# esp32.net
KiCad netlist of a schematic drawn in Altium Designer
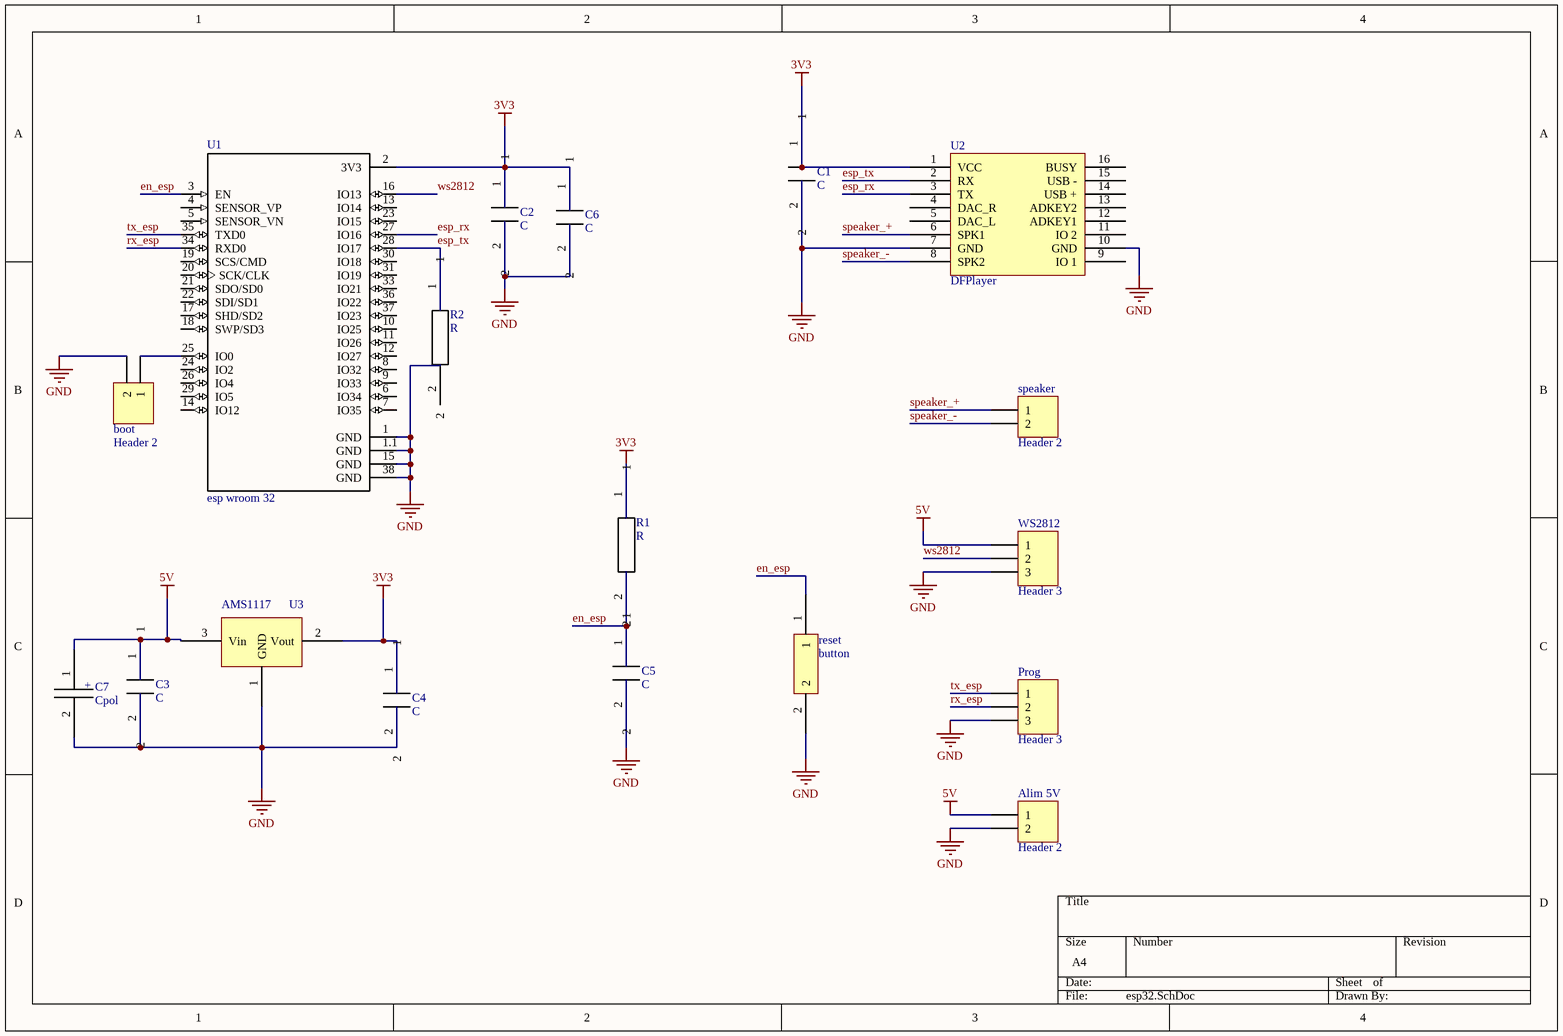
[diagram p0: esp32.SchDoc]

(export (version "E")
  (design (tool "Eeschema 10.0.6"))
  (components
    (comp (ref "Alim 5V")
      (value "Header 2")
      (footprint "HDR1X2")
      (description "Header, 2-Pin")
      (fields (field (name "PUBLISHER") "Altium Limited"))
      (libsource (lib "") (part "Header 2_1"))
    )
    (comp (ref "boot")
      (value "Header 2")
      (footprint "HDR1X2")
      (description "Header, 2-Pin")
      (fields (field (name "PUBLISHER") "Altium Limited"))
      (libsource (lib "Miscellaneous Connectors") (part "Header 2"))
    )
    (comp (ref "C1") (value "C") (footprint "CAP 0805") (libsource (lib "project_sch") (part "C")))
    (comp (ref "C2") (value "C") (footprint "CAP 0805") (libsource (lib "project_sch") (part "C")))
    (comp (ref "C3") (value "C") (footprint "CAP 0805") (libsource (lib "project_sch") (part "C")))
    (comp (ref "C4") (value "C") (footprint "CAP 0805") (libsource (lib "project_sch") (part "C")))
    (comp (ref "C5") (value "C") (footprint "CAP 0805") (libsource (lib "project_sch") (part "C")))
    (comp (ref "C6") (value "C") (footprint "CAP 0805") (libsource (lib "project_sch") (part "C")))
    (comp (ref "C7") (value "Cpol") (footprint "SMD_capacitor") (libsource (lib "project_sch") (part "Cpol")))
    (comp (ref "Prog")
      (value "Header 3")
      (footprint "HDR1X3")
      (description "Header, 3-Pin")
      (fields (field (name "PUBLISHER") "Altium Limited"))
      (libsource (lib "Miscellaneous Connectors") (part "Header 3"))
    )
    (comp (ref "R1") (value "R") (footprint "RES 0805") (libsource (lib "project_sch") (part "R")))
    (comp (ref "R2") (value "R") (footprint "RES 0805") (libsource (lib "project_sch") (part "R")))
    (comp (ref "reset")
      (value "button")
      (footprint "button_pcb")
      (libsource (lib "project_sch") (part "button"))
    )
    (comp (ref "speaker")
      (value "Header 2")
      (footprint "HDR1X2")
      (description "Header, 2-Pin")
      (fields (field (name "PUBLISHER") "Altium Limited"))
      (libsource (lib "") (part "Header 2_1"))
    )
    (comp (ref "U1")
      (value "esp wroom 32")
      (footprint "esp32")
      (description "ESP32-WROOM-32 generic Wi-Fi+BT+BLE MCU module")
      (libsource (lib "project_sch") (part "esp wroom 32"))
    )
    (comp (ref "U2")
      (value "DFPlayer")
      (footprint "DFPlayer")
      (description "serial MP3 module")
      (libsource (lib "project_sch") (part "DFPlayer"))
    )
    (comp (ref "U3")
      (value "AMS1117")
      (footprint "SOT229P700X180-4N")
      (description "1A LOW DROPOUT VOLTAGE REGULATOR")
      (libsource (lib "project_sch") (part "AMS1117"))
    )
    (comp (ref "WS2812")
      (value "Header 3")
      (footprint "HDR1X3")
      (description "Header, 3-Pin")
      (fields (field (name "PUBLISHER") "Altium Limited"))
      (libsource (lib "Miscellaneous Connectors") (part "Header 3"))
    )
  )
  (nets
    (net (code "1") (name "/en_esp") (class "Default")
      (node (ref "C5") (pin "1") (pinfunction "1_1") (pintype "passive"))
      (node (ref "R1") (pin "2") (pinfunction "2_2") (pintype "passive"))
      (node (ref "U1") (pin "3") (pinfunction "EN_3") (pintype "input"))
      (node (ref "reset") (pin "1") (pinfunction "1_1") (pintype "passive"))
    )
    (net (code "2") (name "/esp_rx") (class "Default")
      (node (ref "U1") (pin "27") (pinfunction "IO16_27") (pintype "bidirectional"))
      (node (ref "U2") (pin "3") (pinfunction "TX_3") (pintype "passive"))
    )
    (net (code "3") (name "/esp_tx") (class "Default")
      (node (ref "R2") (pin "1") (pinfunction "1_1") (pintype "passive"))
      (node (ref "U1") (pin "28") (pinfunction "IO17_28") (pintype "bidirectional"))
      (node (ref "U2") (pin "2") (pinfunction "RX_2") (pintype "passive"))
    )
    (net (code "4") (name "/rx_esp") (class "Default")
      (node (ref "Prog") (pin "2") (pinfunction "2_2") (pintype "passive"))
      (node (ref "U1") (pin "34") (pinfunction "RXD0_34") (pintype "bidirectional"))
    )
    (net (code "5") (name "/speaker_+") (class "Default")
      (node (ref "U2") (pin "6") (pinfunction "SPK1_6") (pintype "passive"))
      (node (ref "speaker") (pin "1") (pinfunction "1_1") (pintype "passive"))
    )
    (net (code "6") (name "/speaker_-") (class "Default")
      (node (ref "U2") (pin "8") (pinfunction "SPK2_8") (pintype "passive"))
      (node (ref "speaker") (pin "2") (pinfunction "2_2") (pintype "passive"))
    )
    (net (code "7") (name "/tx_esp") (class "Default")
      (node (ref "Prog") (pin "1") (pinfunction "1_1") (pintype "passive"))
      (node (ref "U1") (pin "35") (pinfunction "TXD0_35") (pintype "bidirectional"))
    )
    (net (code "8") (name "/ws2812") (class "Default")
      (node (ref "U1") (pin "16") (pinfunction "IO13_16") (pintype "bidirectional"))
      (node (ref "WS2812") (pin "2") (pinfunction "2_2") (pintype "passive"))
    )
    (net (code "9") (name "3V3") (class "Default")
      (node (ref "C1") (pin "1") (pinfunction "1_1") (pintype "passive"))
      (node (ref "C2") (pin "1") (pinfunction "1_1") (pintype "passive"))
      (node (ref "C4") (pin "1") (pinfunction "1_1") (pintype "passive"))
      (node (ref "C6") (pin "1") (pinfunction "1_1") (pintype "passive"))
      (node (ref "R1") (pin "1") (pinfunction "1_1") (pintype "passive"))
      (node (ref "U1") (pin "2") (pinfunction "3V3_2") (pintype "power_in"))
      (node (ref "U2") (pin "1") (pinfunction "VCC_1") (pintype "passive"))
      (node (ref "U3") (pin "2") (pinfunction "Vout_2") (pintype "passive"))
    )
    (net (code "10") (name "5V") (class "Default")
      (node (ref "Alim 5V") (pin "1") (pinfunction "1_1") (pintype "passive"))
      (node (ref "C3") (pin "1") (pinfunction "1_1") (pintype "passive"))
      (node (ref "C7") (pin "1") (pintype "passive"))
      (node (ref "U3") (pin "3") (pinfunction "Vin_3") (pintype "passive"))
      (node (ref "WS2812") (pin "1") (pinfunction "1_1") (pintype "passive"))
    )
    (net (code "11") (name "GND") (class "Default")
      (node (ref "Alim 5V") (pin "2") (pinfunction "2_2") (pintype "passive"))
      (node (ref "C1") (pin "2") (pinfunction "2_2") (pintype "passive"))
      (node (ref "C2") (pin "2") (pinfunction "2_2") (pintype "passive"))
      (node (ref "C3") (pin "2") (pinfunction "2_2") (pintype "passive"))
      (node (ref "C4") (pin "2") (pinfunction "2_2") (pintype "passive"))
      (node (ref "C5") (pin "2") (pinfunction "2_2") (pintype "passive"))
      (node (ref "C6") (pin "2") (pinfunction "2_2") (pintype "passive"))
      (node (ref "C7") (pin "2") (pintype "passive"))
      (node (ref "Prog") (pin "3") (pinfunction "3_3") (pintype "passive"))
      (node (ref "R2") (pin "2") (pinfunction "2_2") (pintype "passive"))
      (node (ref "U1") (pin "1") (pinfunction "GND_1") (pintype "power_in"))
      (node (ref "U1") (pin "1.1") (pinfunction "GND_1.1") (pintype "power_in"))
      (node (ref "U1") (pin "15") (pinfunction "GND_15") (pintype "power_in"))
      (node (ref "U1") (pin "38") (pinfunction "GND_38") (pintype "power_in"))
      (node (ref "U2") (pin "10") (pinfunction "GND_10") (pintype "passive"))
      (node (ref "U2") (pin "7") (pinfunction "GND_7") (pintype "passive"))
      (node (ref "U3") (pin "1") (pinfunction "GND_1") (pintype "passive"))
      (node (ref "WS2812") (pin "3") (pinfunction "3_3") (pintype "passive"))
      (node (ref "boot") (pin "2") (pinfunction "2_2") (pintype "passive"))
      (node (ref "reset") (pin "2") (pinfunction "2_2") (pintype "passive"))
    )
    (net (code "12") (name "Net-(U1-IO0)") (class "Default")
      (node (ref "U1") (pin "25") (pinfunction "IO0_25") (pintype "bidirectional"))
      (node (ref "boot") (pin "1") (pinfunction "1_1") (pintype "passive"))
    )
    (net (code "13") (name "unconnected-(U1-IO2-Pad24)") (class "Default")
      (node (ref "U1") (pin "24") (pinfunction "IO2_24") (pintype "bidirectional"))
    )
    (net (code "14") (name "unconnected-(U1-IO4-Pad26)") (class "Default")
      (node (ref "U1") (pin "26") (pinfunction "IO4_26") (pintype "bidirectional"))
    )
    (net (code "15") (name "unconnected-(U1-IO5-Pad29)") (class "Default")
      (node (ref "U1") (pin "29") (pinfunction "IO5_29") (pintype "bidirectional"))
    )
    (net (code "16") (name "unconnected-(U1-IO12-Pad14)") (class "Default")
      (node (ref "U1") (pin "14") (pinfunction "IO12_14") (pintype "bidirectional"))
    )
    (net (code "17") (name "unconnected-(U1-IO14-Pad13)") (class "Default")
      (node (ref "U1") (pin "13") (pinfunction "IO14_13") (pintype "bidirectional"))
    )
    (net (code "18") (name "unconnected-(U1-IO15-Pad23)") (class "Default")
      (node (ref "U1") (pin "23") (pinfunction "IO15_23") (pintype "bidirectional"))
    )
    (net (code "19") (name "unconnected-(U1-IO18-Pad30)") (class "Default")
      (node (ref "U1") (pin "30") (pinfunction "IO18_30") (pintype "bidirectional"))
    )
    (net (code "20") (name "unconnected-(U1-IO19-Pad31)") (class "Default")
      (node (ref "U1") (pin "31") (pinfunction "IO19_31") (pintype "bidirectional"))
    )
    (net (code "21") (name "unconnected-(U1-IO21-Pad33)") (class "Default")
      (node (ref "U1") (pin "33") (pinfunction "IO21_33") (pintype "bidirectional"))
    )
    (net (code "22") (name "unconnected-(U1-IO22-Pad36)") (class "Default")
      (node (ref "U1") (pin "36") (pinfunction "IO22_36") (pintype "bidirectional"))
    )
    (net (code "23") (name "unconnected-(U1-IO23-Pad37)") (class "Default")
      (node (ref "U1") (pin "37") (pinfunction "IO23_37") (pintype "bidirectional"))
    )
    (net (code "24") (name "unconnected-(U1-IO25-Pad10)") (class "Default")
      (node (ref "U1") (pin "10") (pinfunction "IO25_10") (pintype "bidirectional"))
    )
    (net (code "25") (name "unconnected-(U1-IO26-Pad11)") (class "Default")
      (node (ref "U1") (pin "11") (pinfunction "IO26_11") (pintype "bidirectional"))
    )
    (net (code "26") (name "unconnected-(U1-IO27-Pad12)") (class "Default")
      (node (ref "U1") (pin "12") (pinfunction "IO27_12") (pintype "bidirectional"))
    )
    (net (code "27") (name "unconnected-(U1-IO32-Pad8)") (class "Default")
      (node (ref "U1") (pin "8") (pinfunction "IO32_8") (pintype "bidirectional"))
    )
    (net (code "28") (name "unconnected-(U1-IO33-Pad9)") (class "Default")
      (node (ref "U1") (pin "9") (pinfunction "IO33_9") (pintype "bidirectional"))
    )
    (net (code "29") (name "unconnected-(U1-IO34-Pad6)") (class "Default")
      (node (ref "U1") (pin "6") (pinfunction "IO34_6") (pintype "bidirectional"))
    )
    (net (code "30") (name "unconnected-(U1-IO35-Pad7)") (class "Default")
      (node (ref "U1") (pin "7") (pinfunction "IO35_7") (pintype "bidirectional"))
    )
    (net (code "31") (name "unconnected-(U1-SCK{slash}CLK-Pad20)") (class "Default")
      (node (ref "U1") (pin "20") (pinfunction "SCK/CLK_20") (pintype "bidirectional"))
    )
    (net (code "32") (name "unconnected-(U1-SCS{slash}CMD-Pad19)") (class "Default")
      (node (ref "U1") (pin "19") (pinfunction "SCS/CMD_19") (pintype "bidirectional"))
    )
    (net (code "33") (name "unconnected-(U1-SDI{slash}SD1-Pad22)") (class "Default")
      (node (ref "U1") (pin "22") (pinfunction "SDI/SD1_22") (pintype "bidirectional"))
    )
    (net (code "34") (name "unconnected-(U1-SDO{slash}SD0-Pad21)") (class "Default")
      (node (ref "U1") (pin "21") (pinfunction "SDO/SD0_21") (pintype "bidirectional"))
    )
    (net (code "35") (name "unconnected-(U1-SENSOR_VN-Pad5)") (class "Default")
      (node (ref "U1") (pin "5") (pinfunction "SENSOR_VN_5") (pintype "input"))
    )
    (net (code "36") (name "unconnected-(U1-SENSOR_VP-Pad4)") (class "Default")
      (node (ref "U1") (pin "4") (pinfunction "SENSOR_VP_4") (pintype "input"))
    )
    (net (code "37") (name "unconnected-(U1-SHD{slash}SD2-Pad17)") (class "Default")
      (node (ref "U1") (pin "17") (pinfunction "SHD/SD2_17") (pintype "bidirectional"))
    )
    (net (code "38") (name "unconnected-(U1-SWP{slash}SD3-Pad18)") (class "Default")
      (node (ref "U1") (pin "18") (pinfunction "SWP/SD3_18") (pintype "bidirectional"))
    )
    (net (code "39") (name "unconnected-(U2-ADKEY1-Pad12)") (class "Default")
      (node (ref "U2") (pin "12") (pinfunction "ADKEY1_12") (pintype "passive"))
    )
    (net (code "40") (name "unconnected-(U2-ADKEY2-Pad13)") (class "Default")
      (node (ref "U2") (pin "13") (pinfunction "ADKEY2_13") (pintype "passive"))
    )
    (net (code "41") (name "unconnected-(U2-BUSY-Pad16)") (class "Default")
      (node (ref "U2") (pin "16") (pinfunction "BUSY_16") (pintype "passive"))
    )
    (net (code "42") (name "unconnected-(U2-DAC_L-Pad5)") (class "Default")
      (node (ref "U2") (pin "5") (pinfunction "DAC_L_5") (pintype "passive"))
    )
    (net (code "43") (name "unconnected-(U2-DAC_R-Pad4)") (class "Default")
      (node (ref "U2") (pin "4") (pinfunction "DAC_R_4") (pintype "passive"))
    )
    (net (code "44") (name "unconnected-(U2-IO_1-Pad9)") (class "Default")
      (node (ref "U2") (pin "9") (pinfunction "IO_1_9") (pintype "passive"))
    )
    (net (code "45") (name "unconnected-(U2-IO_2-Pad11)") (class "Default")
      (node (ref "U2") (pin "11") (pinfunction "IO_2_11") (pintype "passive"))
    )
    (net (code "46") (name "unconnected-(U2-USB_+-Pad14)") (class "Default")
      (node (ref "U2") (pin "14") (pinfunction "USB_+_14") (pintype "passive"))
    )
    (net (code "47") (name "unconnected-(U2-USB_--Pad15)") (class "Default")
      (node (ref "U2") (pin "15") (pinfunction "USB_-_15") (pintype "passive"))
    )
  )
)
